# domino4_IPP.net
KiCad netlist of a schematic drawn in EAGLE
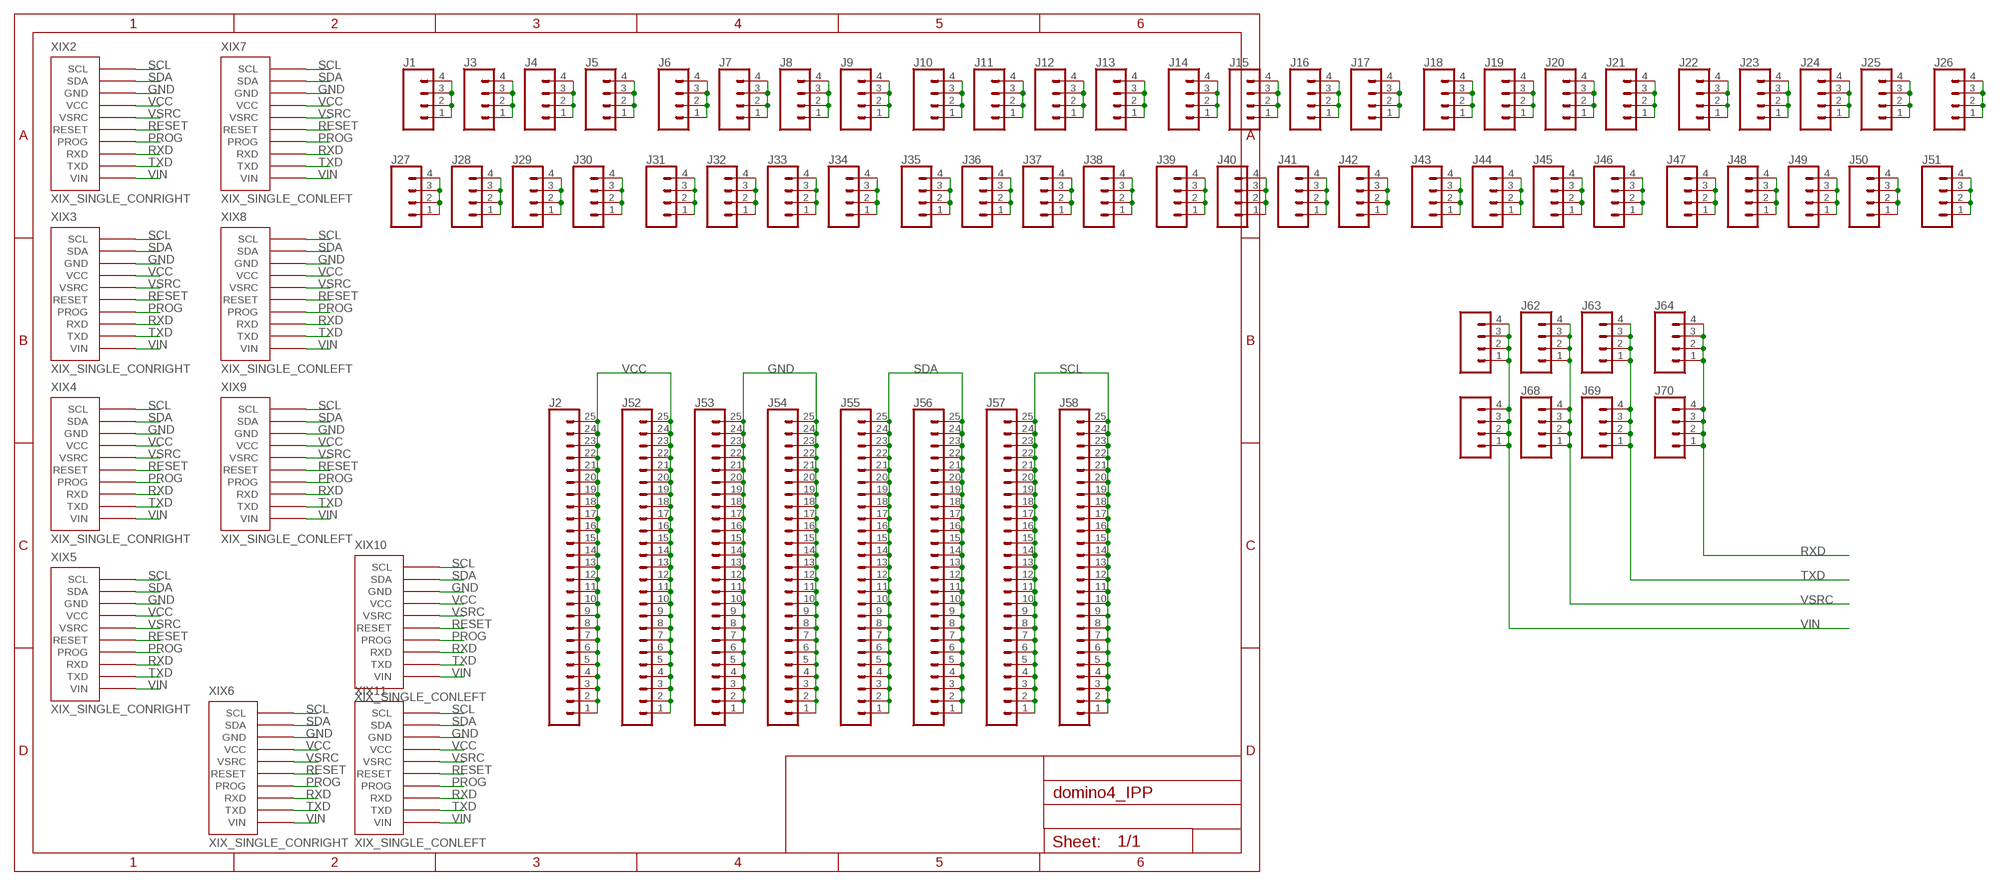
[diagram p0: schematic, sheet 1]

(export (version "E")
  (design (tool "Eeschema 10.0.6"))
  (components
    (comp (ref "J1")
      (value "CONN_04PTH")
      (footprint "eagle-import:1X04")
      (libsource (lib "eagle-import") (part "CONN_04PTH"))
    )
    (comp (ref "J2")
      (value "CONN_25")
      (footprint "eagle-import:1X25")
      (libsource (lib "eagle-import") (part "CONN_25"))
    )
    (comp (ref "J3")
      (value "CONN_04PTH")
      (footprint "eagle-import:1X04")
      (libsource (lib "eagle-import") (part "CONN_04PTH"))
    )
    (comp (ref "J4")
      (value "CONN_04PTH")
      (footprint "eagle-import:1X04")
      (libsource (lib "eagle-import") (part "CONN_04PTH"))
    )
    (comp (ref "J5")
      (value "CONN_04PTH")
      (footprint "eagle-import:1X04")
      (libsource (lib "eagle-import") (part "CONN_04PTH"))
    )
    (comp (ref "J6")
      (value "CONN_04PTH")
      (footprint "eagle-import:1X04")
      (libsource (lib "eagle-import") (part "CONN_04PTH"))
    )
    (comp (ref "J7")
      (value "CONN_04PTH")
      (footprint "eagle-import:1X04")
      (libsource (lib "eagle-import") (part "CONN_04PTH"))
    )
    (comp (ref "J8")
      (value "CONN_04PTH")
      (footprint "eagle-import:1X04")
      (libsource (lib "eagle-import") (part "CONN_04PTH"))
    )
    (comp (ref "J9")
      (value "CONN_04PTH")
      (footprint "eagle-import:1X04")
      (libsource (lib "eagle-import") (part "CONN_04PTH"))
    )
    (comp (ref "J10")
      (value "CONN_04PTH")
      (footprint "eagle-import:1X04")
      (libsource (lib "eagle-import") (part "CONN_04PTH"))
    )
    (comp (ref "J11")
      (value "CONN_04PTH")
      (footprint "eagle-import:1X04")
      (libsource (lib "eagle-import") (part "CONN_04PTH"))
    )
    (comp (ref "J12")
      (value "CONN_04PTH")
      (footprint "eagle-import:1X04")
      (libsource (lib "eagle-import") (part "CONN_04PTH"))
    )
    (comp (ref "J13")
      (value "CONN_04PTH")
      (footprint "eagle-import:1X04")
      (libsource (lib "eagle-import") (part "CONN_04PTH"))
    )
    (comp (ref "J14")
      (value "CONN_04PTH")
      (footprint "eagle-import:1X04")
      (libsource (lib "eagle-import") (part "CONN_04PTH"))
    )
    (comp (ref "J15")
      (value "CONN_04PTH")
      (footprint "eagle-import:1X04")
      (libsource (lib "eagle-import") (part "CONN_04PTH"))
    )
    (comp (ref "J16")
      (value "CONN_04PTH")
      (footprint "eagle-import:1X04")
      (libsource (lib "eagle-import") (part "CONN_04PTH"))
    )
    (comp (ref "J17")
      (value "CONN_04PTH")
      (footprint "eagle-import:1X04")
      (libsource (lib "eagle-import") (part "CONN_04PTH"))
    )
    (comp (ref "J18")
      (value "CONN_04PTH")
      (footprint "eagle-import:1X04")
      (libsource (lib "eagle-import") (part "CONN_04PTH"))
    )
    (comp (ref "J19")
      (value "CONN_04PTH")
      (footprint "eagle-import:1X04")
      (libsource (lib "eagle-import") (part "CONN_04PTH"))
    )
    (comp (ref "J20")
      (value "CONN_04PTH")
      (footprint "eagle-import:1X04")
      (libsource (lib "eagle-import") (part "CONN_04PTH"))
    )
    (comp (ref "J21")
      (value "CONN_04PTH")
      (footprint "eagle-import:1X04")
      (libsource (lib "eagle-import") (part "CONN_04PTH"))
    )
    (comp (ref "J22")
      (value "CONN_04PTH")
      (footprint "eagle-import:1X04")
      (libsource (lib "eagle-import") (part "CONN_04PTH"))
    )
    (comp (ref "J23")
      (value "CONN_04PTH")
      (footprint "eagle-import:1X04")
      (libsource (lib "eagle-import") (part "CONN_04PTH"))
    )
    (comp (ref "J24")
      (value "CONN_04PTH")
      (footprint "eagle-import:1X04")
      (libsource (lib "eagle-import") (part "CONN_04PTH"))
    )
    (comp (ref "J25")
      (value "CONN_04PTH")
      (footprint "eagle-import:1X04")
      (libsource (lib "eagle-import") (part "CONN_04PTH"))
    )
    (comp (ref "J26")
      (value "CONN_04PTH")
      (footprint "eagle-import:1X04")
      (libsource (lib "eagle-import") (part "CONN_04PTH"))
    )
    (comp (ref "J27")
      (value "CONN_04PTH")
      (footprint "eagle-import:1X04")
      (libsource (lib "eagle-import") (part "CONN_04PTH"))
    )
    (comp (ref "J28")
      (value "CONN_04PTH")
      (footprint "eagle-import:1X04")
      (libsource (lib "eagle-import") (part "CONN_04PTH"))
    )
    (comp (ref "J29")
      (value "CONN_04PTH")
      (footprint "eagle-import:1X04")
      (libsource (lib "eagle-import") (part "CONN_04PTH"))
    )
    (comp (ref "J30")
      (value "CONN_04PTH")
      (footprint "eagle-import:1X04")
      (libsource (lib "eagle-import") (part "CONN_04PTH"))
    )
    (comp (ref "J31")
      (value "CONN_04PTH")
      (footprint "eagle-import:1X04")
      (libsource (lib "eagle-import") (part "CONN_04PTH"))
    )
    (comp (ref "J32")
      (value "CONN_04PTH")
      (footprint "eagle-import:1X04")
      (libsource (lib "eagle-import") (part "CONN_04PTH"))
    )
    (comp (ref "J33")
      (value "CONN_04PTH")
      (footprint "eagle-import:1X04")
      (libsource (lib "eagle-import") (part "CONN_04PTH"))
    )
    (comp (ref "J34")
      (value "CONN_04PTH")
      (footprint "eagle-import:1X04")
      (libsource (lib "eagle-import") (part "CONN_04PTH"))
    )
    (comp (ref "J35")
      (value "CONN_04PTH")
      (footprint "eagle-import:1X04")
      (libsource (lib "eagle-import") (part "CONN_04PTH"))
    )
    (comp (ref "J36")
      (value "CONN_04PTH")
      (footprint "eagle-import:1X04")
      (libsource (lib "eagle-import") (part "CONN_04PTH"))
    )
    (comp (ref "J37")
      (value "CONN_04PTH")
      (footprint "eagle-import:1X04")
      (libsource (lib "eagle-import") (part "CONN_04PTH"))
    )
    (comp (ref "J38")
      (value "CONN_04PTH")
      (footprint "eagle-import:1X04")
      (libsource (lib "eagle-import") (part "CONN_04PTH"))
    )
    (comp (ref "J39")
      (value "CONN_04PTH")
      (footprint "eagle-import:1X04")
      (libsource (lib "eagle-import") (part "CONN_04PTH"))
    )
    (comp (ref "J40")
      (value "CONN_04PTH")
      (footprint "eagle-import:1X04")
      (libsource (lib "eagle-import") (part "CONN_04PTH"))
    )
    (comp (ref "J41")
      (value "CONN_04PTH")
      (footprint "eagle-import:1X04")
      (libsource (lib "eagle-import") (part "CONN_04PTH"))
    )
    (comp (ref "J42")
      (value "CONN_04PTH")
      (footprint "eagle-import:1X04")
      (libsource (lib "eagle-import") (part "CONN_04PTH"))
    )
    (comp (ref "J43")
      (value "CONN_04PTH")
      (footprint "eagle-import:1X04")
      (libsource (lib "eagle-import") (part "CONN_04PTH"))
    )
    (comp (ref "J44")
      (value "CONN_04PTH")
      (footprint "eagle-import:1X04")
      (libsource (lib "eagle-import") (part "CONN_04PTH"))
    )
    (comp (ref "J45")
      (value "CONN_04PTH")
      (footprint "eagle-import:1X04")
      (libsource (lib "eagle-import") (part "CONN_04PTH"))
    )
    (comp (ref "J46")
      (value "CONN_04PTH")
      (footprint "eagle-import:1X04")
      (libsource (lib "eagle-import") (part "CONN_04PTH"))
    )
    (comp (ref "J47")
      (value "CONN_04PTH")
      (footprint "eagle-import:1X04")
      (libsource (lib "eagle-import") (part "CONN_04PTH"))
    )
    (comp (ref "J48")
      (value "CONN_04PTH")
      (footprint "eagle-import:1X04")
      (libsource (lib "eagle-import") (part "CONN_04PTH"))
    )
    (comp (ref "J49")
      (value "CONN_04PTH")
      (footprint "eagle-import:1X04")
      (libsource (lib "eagle-import") (part "CONN_04PTH"))
    )
    (comp (ref "J50")
      (value "CONN_04PTH")
      (footprint "eagle-import:1X04")
      (libsource (lib "eagle-import") (part "CONN_04PTH"))
    )
    (comp (ref "J51")
      (value "CONN_04PTH")
      (footprint "eagle-import:1X04")
      (libsource (lib "eagle-import") (part "CONN_04PTH"))
    )
    (comp (ref "J52")
      (value "CONN_25")
      (footprint "eagle-import:1X25")
      (libsource (lib "eagle-import") (part "CONN_25"))
    )
    (comp (ref "J53")
      (value "CONN_25")
      (footprint "eagle-import:1X25")
      (libsource (lib "eagle-import") (part "CONN_25"))
    )
    (comp (ref "J54")
      (value "CONN_25")
      (footprint "eagle-import:1X25")
      (libsource (lib "eagle-import") (part "CONN_25"))
    )
    (comp (ref "J55")
      (value "CONN_25")
      (footprint "eagle-import:1X25")
      (libsource (lib "eagle-import") (part "CONN_25"))
    )
    (comp (ref "J56")
      (value "CONN_25")
      (footprint "eagle-import:1X25")
      (libsource (lib "eagle-import") (part "CONN_25"))
    )
    (comp (ref "J57")
      (value "CONN_25")
      (footprint "eagle-import:1X25")
      (libsource (lib "eagle-import") (part "CONN_25"))
    )
    (comp (ref "J58")
      (value "CONN_25")
      (footprint "eagle-import:1X25")
      (libsource (lib "eagle-import") (part "CONN_25"))
    )
    (comp (ref "J61")
      (value "CONN_04PTH")
      (footprint "eagle-import:1X04")
      (libsource (lib "eagle-import") (part "CONN_04PTH"))
    )
    (comp (ref "J62")
      (value "CONN_04PTH")
      (footprint "eagle-import:1X04")
      (libsource (lib "eagle-import") (part "CONN_04PTH"))
    )
    (comp (ref "J63")
      (value "CONN_04PTH")
      (footprint "eagle-import:1X04")
      (libsource (lib "eagle-import") (part "CONN_04PTH"))
    )
    (comp (ref "J64")
      (value "CONN_04PTH")
      (footprint "eagle-import:1X04")
      (libsource (lib "eagle-import") (part "CONN_04PTH"))
    )
    (comp (ref "J67")
      (value "CONN_04PTH")
      (footprint "eagle-import:1X04")
      (libsource (lib "eagle-import") (part "CONN_04PTH"))
    )
    (comp (ref "J68")
      (value "CONN_04PTH")
      (footprint "eagle-import:1X04")
      (libsource (lib "eagle-import") (part "CONN_04PTH"))
    )
    (comp (ref "J69")
      (value "CONN_04PTH")
      (footprint "eagle-import:1X04")
      (libsource (lib "eagle-import") (part "CONN_04PTH"))
    )
    (comp (ref "J70")
      (value "CONN_04PTH")
      (footprint "eagle-import:1X04")
      (libsource (lib "eagle-import") (part "CONN_04PTH"))
    )
    (comp (ref "XIX2")
      (value "XIX_SINGLE_CONRIGHT")
      (footprint "eagle-import:XIX_SINGLE_CON_RIGHT")
      (libsource (lib "eagle-import") (part "XIX_SINGLE_CONRIGHT"))
    )
    (comp (ref "XIX3")
      (value "XIX_SINGLE_CONRIGHT")
      (footprint "eagle-import:XIX_SINGLE_CON_RIGHT")
      (libsource (lib "eagle-import") (part "XIX_SINGLE_CONRIGHT"))
    )
    (comp (ref "XIX4")
      (value "XIX_SINGLE_CONRIGHT")
      (footprint "eagle-import:XIX_SINGLE_CON_RIGHT")
      (libsource (lib "eagle-import") (part "XIX_SINGLE_CONRIGHT"))
    )
    (comp (ref "XIX5")
      (value "XIX_SINGLE_CONRIGHT")
      (footprint "eagle-import:XIX_SINGLE_CON_RIGHT")
      (libsource (lib "eagle-import") (part "XIX_SINGLE_CONRIGHT"))
    )
    (comp (ref "XIX6")
      (value "XIX_SINGLE_CONRIGHT")
      (footprint "eagle-import:XIX_SINGLE_CON_RIGHT")
      (libsource (lib "eagle-import") (part "XIX_SINGLE_CONRIGHT"))
    )
    (comp (ref "XIX7")
      (value "XIX_SINGLE_CONLEFT")
      (footprint "eagle-import:XIX_SINGLE_CON_LEFT")
      (libsource (lib "eagle-import") (part "XIX_SINGLE_CONLEFT"))
    )
    (comp (ref "XIX8")
      (value "XIX_SINGLE_CONLEFT")
      (footprint "eagle-import:XIX_SINGLE_CON_LEFT")
      (libsource (lib "eagle-import") (part "XIX_SINGLE_CONLEFT"))
    )
    (comp (ref "XIX9")
      (value "XIX_SINGLE_CONLEFT")
      (footprint "eagle-import:XIX_SINGLE_CON_LEFT")
      (libsource (lib "eagle-import") (part "XIX_SINGLE_CONLEFT"))
    )
    (comp (ref "XIX10")
      (value "XIX_SINGLE_CONLEFT")
      (footprint "eagle-import:XIX_SINGLE_CON_LEFT")
      (libsource (lib "eagle-import") (part "XIX_SINGLE_CONLEFT"))
    )
    (comp (ref "XIX11")
      (value "XIX_SINGLE_CONLEFT")
      (footprint "eagle-import:XIX_SINGLE_CON_LEFT")
      (libsource (lib "eagle-import") (part "XIX_SINGLE_CONLEFT"))
    )
  )
  (nets
    (net (code "1") (name "/GND") (class "Default")
      (node (ref "J53") (pin "1") (pinfunction "1_1") (pintype "passive"))
      (node (ref "J53") (pin "10") (pinfunction "10_10") (pintype "passive"))
      (node (ref "J53") (pin "11") (pinfunction "11_11") (pintype "passive"))
      (node (ref "J53") (pin "12") (pinfunction "12_12") (pintype "passive"))
      (node (ref "J53") (pin "13") (pinfunction "13_13") (pintype "passive"))
      (node (ref "J53") (pin "14") (pinfunction "14_14") (pintype "passive"))
      (node (ref "J53") (pin "15") (pinfunction "15_15") (pintype "passive"))
      (node (ref "J53") (pin "16") (pinfunction "16_16") (pintype "passive"))
      (node (ref "J53") (pin "17") (pinfunction "17_17") (pintype "passive"))
      (node (ref "J53") (pin "18") (pinfunction "18_18") (pintype "passive"))
      (node (ref "J53") (pin "19") (pinfunction "19_19") (pintype "passive"))
      (node (ref "J53") (pin "2") (pinfunction "2_2") (pintype "passive"))
      (node (ref "J53") (pin "20") (pinfunction "20_20") (pintype "passive"))
      (node (ref "J53") (pin "21") (pinfunction "21_21") (pintype "passive"))
      (node (ref "J53") (pin "22") (pinfunction "22_22") (pintype "passive"))
      (node (ref "J53") (pin "23") (pinfunction "23_23") (pintype "passive"))
      (node (ref "J53") (pin "24") (pinfunction "24_24") (pintype "passive"))
      (node (ref "J53") (pin "25") (pinfunction "25_25") (pintype "passive"))
      (node (ref "J53") (pin "3") (pinfunction "3_3") (pintype "passive"))
      (node (ref "J53") (pin "4") (pinfunction "4_4") (pintype "passive"))
      (node (ref "J53") (pin "5") (pinfunction "5_5") (pintype "passive"))
      (node (ref "J53") (pin "6") (pinfunction "6_6") (pintype "passive"))
      (node (ref "J53") (pin "7") (pinfunction "7_7") (pintype "passive"))
      (node (ref "J53") (pin "8") (pinfunction "8_8") (pintype "passive"))
      (node (ref "J53") (pin "9") (pinfunction "9_9") (pintype "passive"))
      (node (ref "J54") (pin "1") (pinfunction "1_1") (pintype "passive"))
      (node (ref "J54") (pin "10") (pinfunction "10_10") (pintype "passive"))
      (node (ref "J54") (pin "11") (pinfunction "11_11") (pintype "passive"))
      (node (ref "J54") (pin "12") (pinfunction "12_12") (pintype "passive"))
      (node (ref "J54") (pin "13") (pinfunction "13_13") (pintype "passive"))
      (node (ref "J54") (pin "14") (pinfunction "14_14") (pintype "passive"))
      (node (ref "J54") (pin "15") (pinfunction "15_15") (pintype "passive"))
      (node (ref "J54") (pin "16") (pinfunction "16_16") (pintype "passive"))
      (node (ref "J54") (pin "17") (pinfunction "17_17") (pintype "passive"))
      (node (ref "J54") (pin "18") (pinfunction "18_18") (pintype "passive"))
      (node (ref "J54") (pin "19") (pinfunction "19_19") (pintype "passive"))
      (node (ref "J54") (pin "2") (pinfunction "2_2") (pintype "passive"))
      (node (ref "J54") (pin "20") (pinfunction "20_20") (pintype "passive"))
      (node (ref "J54") (pin "21") (pinfunction "21_21") (pintype "passive"))
      (node (ref "J54") (pin "22") (pinfunction "22_22") (pintype "passive"))
      (node (ref "J54") (pin "23") (pinfunction "23_23") (pintype "passive"))
      (node (ref "J54") (pin "24") (pinfunction "24_24") (pintype "passive"))
      (node (ref "J54") (pin "25") (pinfunction "25_25") (pintype "passive"))
      (node (ref "J54") (pin "3") (pinfunction "3_3") (pintype "passive"))
      (node (ref "J54") (pin "4") (pinfunction "4_4") (pintype "passive"))
      (node (ref "J54") (pin "5") (pinfunction "5_5") (pintype "passive"))
      (node (ref "J54") (pin "6") (pinfunction "6_6") (pintype "passive"))
      (node (ref "J54") (pin "7") (pinfunction "7_7") (pintype "passive"))
      (node (ref "J54") (pin "8") (pinfunction "8_8") (pintype "passive"))
      (node (ref "J54") (pin "9") (pinfunction "9_9") (pintype "passive"))
      (node (ref "XIX10") (pin "GND@1") (pinfunction "GND_GND@1") (pintype "power_in"))
      (node (ref "XIX11") (pin "GND@1") (pinfunction "GND_GND@1") (pintype "power_in"))
      (node (ref "XIX2") (pin "GND@4") (pinfunction "GND_GND@4") (pintype "power_in"))
      (node (ref "XIX3") (pin "GND@4") (pinfunction "GND_GND@4") (pintype "power_in"))
      (node (ref "XIX4") (pin "GND@4") (pinfunction "GND_GND@4") (pintype "power_in"))
      (node (ref "XIX5") (pin "GND@4") (pinfunction "GND_GND@4") (pintype "power_in"))
      (node (ref "XIX6") (pin "GND@4") (pinfunction "GND_GND@4") (pintype "power_in"))
      (node (ref "XIX7") (pin "GND@1") (pinfunction "GND_GND@1") (pintype "power_in"))
      (node (ref "XIX8") (pin "GND@1") (pinfunction "GND_GND@1") (pintype "power_in"))
      (node (ref "XIX9") (pin "GND@1") (pinfunction "GND_GND@1") (pintype "power_in"))
    )
    (net (code "2") (name "/PROG") (class "Default")
      (node (ref "XIX10") (pin "PROG@2") (pinfunction "PROG_PROG@2") (pintype "bidirectional"))
      (node (ref "XIX11") (pin "PROG@2") (pinfunction "PROG_PROG@2") (pintype "bidirectional"))
      (node (ref "XIX2") (pin "PROG@8") (pinfunction "PROG_PROG@8") (pintype "bidirectional"))
      (node (ref "XIX3") (pin "PROG@8") (pinfunction "PROG_PROG@8") (pintype "bidirectional"))
      (node (ref "XIX4") (pin "PROG@8") (pinfunction "PROG_PROG@8") (pintype "bidirectional"))
      (node (ref "XIX5") (pin "PROG@8") (pinfunction "PROG_PROG@8") (pintype "bidirectional"))
      (node (ref "XIX6") (pin "PROG@8") (pinfunction "PROG_PROG@8") (pintype "bidirectional"))
      (node (ref "XIX7") (pin "PROG@2") (pinfunction "PROG_PROG@2") (pintype "bidirectional"))
      (node (ref "XIX8") (pin "PROG@2") (pinfunction "PROG_PROG@2") (pintype "bidirectional"))
      (node (ref "XIX9") (pin "PROG@2") (pinfunction "PROG_PROG@2") (pintype "bidirectional"))
    )
    (net (code "3") (name "/RESET") (class "Default")
      (node (ref "XIX10") (pin "RESET@2") (pinfunction "RESET_RESET@2") (pintype "bidirectional"))
      (node (ref "XIX11") (pin "RESET@2") (pinfunction "RESET_RESET@2") (pintype "bidirectional"))
      (node (ref "XIX2") (pin "RESET@8") (pinfunction "RESET_RESET@8") (pintype "bidirectional"))
      (node (ref "XIX3") (pin "RESET@8") (pinfunction "RESET_RESET@8") (pintype "bidirectional"))
      (node (ref "XIX4") (pin "RESET@8") (pinfunction "RESET_RESET@8") (pintype "bidirectional"))
      (node (ref "XIX5") (pin "RESET@8") (pinfunction "RESET_RESET@8") (pintype "bidirectional"))
      (node (ref "XIX6") (pin "RESET@8") (pinfunction "RESET_RESET@8") (pintype "bidirectional"))
      (node (ref "XIX7") (pin "RESET@2") (pinfunction "RESET_RESET@2") (pintype "bidirectional"))
      (node (ref "XIX8") (pin "RESET@2") (pinfunction "RESET_RESET@2") (pintype "bidirectional"))
      (node (ref "XIX9") (pin "RESET@2") (pinfunction "RESET_RESET@2") (pintype "bidirectional"))
    )
    (net (code "4") (name "/RXD") (class "Default")
      (node (ref "J64") (pin "1") (pinfunction "1_1") (pintype "passive"))
      (node (ref "J64") (pin "2") (pinfunction "2_2") (pintype "passive"))
      (node (ref "J64") (pin "3") (pinfunction "3_3") (pintype "passive"))
      (node (ref "J64") (pin "4") (pinfunction "4_4") (pintype "passive"))
      (node (ref "J70") (pin "1") (pinfunction "1_1") (pintype "passive"))
      (node (ref "J70") (pin "2") (pinfunction "2_2") (pintype "passive"))
      (node (ref "J70") (pin "3") (pinfunction "3_3") (pintype "passive"))
      (node (ref "J70") (pin "4") (pinfunction "4_4") (pintype "passive"))
      (node (ref "XIX10") (pin "RXD@2") (pinfunction "RXD_RXD@2") (pintype "bidirectional"))
      (node (ref "XIX11") (pin "RXD@2") (pinfunction "RXD_RXD@2") (pintype "bidirectional"))
      (node (ref "XIX2") (pin "RXD@8") (pinfunction "RXD_RXD@8") (pintype "bidirectional"))
      (node (ref "XIX3") (pin "RXD@8") (pinfunction "RXD_RXD@8") (pintype "bidirectional"))
      (node (ref "XIX4") (pin "RXD@8") (pinfunction "RXD_RXD@8") (pintype "bidirectional"))
      (node (ref "XIX5") (pin "RXD@8") (pinfunction "RXD_RXD@8") (pintype "bidirectional"))
      (node (ref "XIX6") (pin "RXD@8") (pinfunction "RXD_RXD@8") (pintype "bidirectional"))
      (node (ref "XIX7") (pin "RXD@2") (pinfunction "RXD_RXD@2") (pintype "bidirectional"))
      (node (ref "XIX8") (pin "RXD@2") (pinfunction "RXD_RXD@2") (pintype "bidirectional"))
      (node (ref "XIX9") (pin "RXD@2") (pinfunction "RXD_RXD@2") (pintype "bidirectional"))
    )
    (net (code "5") (name "/SCL") (class "Default")
      (node (ref "J57") (pin "1") (pinfunction "1_1") (pintype "passive"))
      (node (ref "J57") (pin "10") (pinfunction "10_10") (pintype "passive"))
      (node (ref "J57") (pin "11") (pinfunction "11_11") (pintype "passive"))
      (node (ref "J57") (pin "12") (pinfunction "12_12") (pintype "passive"))
      (node (ref "J57") (pin "13") (pinfunction "13_13") (pintype "passive"))
      (node (ref "J57") (pin "14") (pinfunction "14_14") (pintype "passive"))
      (node (ref "J57") (pin "15") (pinfunction "15_15") (pintype "passive"))
      (node (ref "J57") (pin "16") (pinfunction "16_16") (pintype "passive"))
      (node (ref "J57") (pin "17") (pinfunction "17_17") (pintype "passive"))
      (node (ref "J57") (pin "18") (pinfunction "18_18") (pintype "passive"))
      (node (ref "J57") (pin "19") (pinfunction "19_19") (pintype "passive"))
      (node (ref "J57") (pin "2") (pinfunction "2_2") (pintype "passive"))
      (node (ref "J57") (pin "20") (pinfunction "20_20") (pintype "passive"))
      (node (ref "J57") (pin "21") (pinfunction "21_21") (pintype "passive"))
      (node (ref "J57") (pin "22") (pinfunction "22_22") (pintype "passive"))
      (node (ref "J57") (pin "23") (pinfunction "23_23") (pintype "passive"))
      (node (ref "J57") (pin "24") (pinfunction "24_24") (pintype "passive"))
      (node (ref "J57") (pin "25") (pinfunction "25_25") (pintype "passive"))
      (node (ref "J57") (pin "3") (pinfunction "3_3") (pintype "passive"))
      (node (ref "J57") (pin "4") (pinfunction "4_4") (pintype "passive"))
      (node (ref "J57") (pin "5") (pinfunction "5_5") (pintype "passive"))
      (node (ref "J57") (pin "6") (pinfunction "6_6") (pintype "passive"))
      (node (ref "J57") (pin "7") (pinfunction "7_7") (pintype "passive"))
      (node (ref "J57") (pin "8") (pinfunction "8_8") (pintype "passive"))
      (node (ref "J57") (pin "9") (pinfunction "9_9") (pintype "passive"))
      (node (ref "J58") (pin "1") (pinfunction "1_1") (pintype "passive"))
      (node (ref "J58") (pin "10") (pinfunction "10_10") (pintype "passive"))
      (node (ref "J58") (pin "11") (pinfunction "11_11") (pintype "passive"))
      (node (ref "J58") (pin "12") (pinfunction "12_12") (pintype "passive"))
      (node (ref "J58") (pin "13") (pinfunction "13_13") (pintype "passive"))
      (node (ref "J58") (pin "14") (pinfunction "14_14") (pintype "passive"))
      (node (ref "J58") (pin "15") (pinfunction "15_15") (pintype "passive"))
      (node (ref "J58") (pin "16") (pinfunction "16_16") (pintype "passive"))
      (node (ref "J58") (pin "17") (pinfunction "17_17") (pintype "passive"))
      (node (ref "J58") (pin "18") (pinfunction "18_18") (pintype "passive"))
      (node (ref "J58") (pin "19") (pinfunction "19_19") (pintype "passive"))
      (node (ref "J58") (pin "2") (pinfunction "2_2") (pintype "passive"))
      (node (ref "J58") (pin "20") (pinfunction "20_20") (pintype "passive"))
      (node (ref "J58") (pin "21") (pinfunction "21_21") (pintype "passive"))
      (node (ref "J58") (pin "22") (pinfunction "22_22") (pintype "passive"))
      (node (ref "J58") (pin "23") (pinfunction "23_23") (pintype "passive"))
      (node (ref "J58") (pin "24") (pinfunction "24_24") (pintype "passive"))
      (node (ref "J58") (pin "25") (pinfunction "25_25") (pintype "passive"))
      (node (ref "J58") (pin "3") (pinfunction "3_3") (pintype "passive"))
      (node (ref "J58") (pin "4") (pinfunction "4_4") (pintype "passive"))
      (node (ref "J58") (pin "5") (pinfunction "5_5") (pintype "passive"))
      (node (ref "J58") (pin "6") (pinfunction "6_6") (pintype "passive"))
      (node (ref "J58") (pin "7") (pinfunction "7_7") (pintype "passive"))
      (node (ref "J58") (pin "8") (pinfunction "8_8") (pintype "passive"))
      (node (ref "J58") (pin "9") (pinfunction "9_9") (pintype "passive"))
      (node (ref "XIX10") (pin "SCL@1") (pinfunction "SCL_SCL@1") (pintype "bidirectional"))
      (node (ref "XIX11") (pin "SCL@1") (pinfunction "SCL_SCL@1") (pintype "bidirectional"))
      (node (ref "XIX2") (pin "SCL@4") (pinfunction "SCL_SCL@4") (pintype "bidirectional"))
      (node (ref "XIX3") (pin "SCL@4") (pinfunction "SCL_SCL@4") (pintype "bidirectional"))
      (node (ref "XIX4") (pin "SCL@4") (pinfunction "SCL_SCL@4") (pintype "bidirectional"))
      (node (ref "XIX5") (pin "SCL@4") (pinfunction "SCL_SCL@4") (pintype "bidirectional"))
      (node (ref "XIX6") (pin "SCL@4") (pinfunction "SCL_SCL@4") (pintype "bidirectional"))
      (node (ref "XIX7") (pin "SCL@1") (pinfunction "SCL_SCL@1") (pintype "bidirectional"))
      (node (ref "XIX8") (pin "SCL@1") (pinfunction "SCL_SCL@1") (pintype "bidirectional"))
      (node (ref "XIX9") (pin "SCL@1") (pinfunction "SCL_SCL@1") (pintype "bidirectional"))
    )
    (net (code "6") (name "/SDA") (class "Default")
      (node (ref "J55") (pin "1") (pinfunction "1_1") (pintype "passive"))
      (node (ref "J55") (pin "10") (pinfunction "10_10") (pintype "passive"))
      (node (ref "J55") (pin "11") (pinfunction "11_11") (pintype "passive"))
      (node (ref "J55") (pin "12") (pinfunction "12_12") (pintype "passive"))
      (node (ref "J55") (pin "13") (pinfunction "13_13") (pintype "passive"))
      (node (ref "J55") (pin "14") (pinfunction "14_14") (pintype "passive"))
      (node (ref "J55") (pin "15") (pinfunction "15_15") (pintype "passive"))
      (node (ref "J55") (pin "16") (pinfunction "16_16") (pintype "passive"))
      (node (ref "J55") (pin "17") (pinfunction "17_17") (pintype "passive"))
      (node (ref "J55") (pin "18") (pinfunction "18_18") (pintype "passive"))
      (node (ref "J55") (pin "19") (pinfunction "19_19") (pintype "passive"))
      (node (ref "J55") (pin "2") (pinfunction "2_2") (pintype "passive"))
      (node (ref "J55") (pin "20") (pinfunction "20_20") (pintype "passive"))
      (node (ref "J55") (pin "21") (pinfunction "21_21") (pintype "passive"))
      (node (ref "J55") (pin "22") (pinfunction "22_22") (pintype "passive"))
      (node (ref "J55") (pin "23") (pinfunction "23_23") (pintype "passive"))
      (node (ref "J55") (pin "24") (pinfunction "24_24") (pintype "passive"))
      (node (ref "J55") (pin "25") (pinfunction "25_25") (pintype "passive"))
      (node (ref "J55") (pin "3") (pinfunction "3_3") (pintype "passive"))
      (node (ref "J55") (pin "4") (pinfunction "4_4") (pintype "passive"))
      (node (ref "J55") (pin "5") (pinfunction "5_5") (pintype "passive"))
      (node (ref "J55") (pin "6") (pinfunction "6_6") (pintype "passive"))
      (node (ref "J55") (pin "7") (pinfunction "7_7") (pintype "passive"))
      (node (ref "J55") (pin "8") (pinfunction "8_8") (pintype "passive"))
      (node (ref "J55") (pin "9") (pinfunction "9_9") (pintype "passive"))
      (node (ref "J56") (pin "1") (pinfunction "1_1") (pintype "passive"))
      (node (ref "J56") (pin "10") (pinfunction "10_10") (pintype "passive"))
      (node (ref "J56") (pin "11") (pinfunction "11_11") (pintype "passive"))
      (node (ref "J56") (pin "12") (pinfunction "12_12") (pintype "passive"))
      (node (ref "J56") (pin "13") (pinfunction "13_13") (pintype "passive"))
      (node (ref "J56") (pin "14") (pinfunction "14_14") (pintype "passive"))
      (node (ref "J56") (pin "15") (pinfunction "15_15") (pintype "passive"))
      (node (ref "J56") (pin "16") (pinfunction "16_16") (pintype "passive"))
      (node (ref "J56") (pin "17") (pinfunction "17_17") (pintype "passive"))
      (node (ref "J56") (pin "18") (pinfunction "18_18") (pintype "passive"))
      (node (ref "J56") (pin "19") (pinfunction "19_19") (pintype "passive"))
      (node (ref "J56") (pin "2") (pinfunction "2_2") (pintype "passive"))
      (node (ref "J56") (pin "20") (pinfunction "20_20") (pintype "passive"))
      (node (ref "J56") (pin "21") (pinfunction "21_21") (pintype "passive"))
      (node (ref "J56") (pin "22") (pinfunction "22_22") (pintype "passive"))
      (node (ref "J56") (pin "23") (pinfunction "23_23") (pintype "passive"))
      (node (ref "J56") (pin "24") (pinfunction "24_24") (pintype "passive"))
      (node (ref "J56") (pin "25") (pinfunction "25_25") (pintype "passive"))
      (node (ref "J56") (pin "3") (pinfunction "3_3") (pintype "passive"))
      (node (ref "J56") (pin "4") (pinfunction "4_4") (pintype "passive"))
      (node (ref "J56") (pin "5") (pinfunction "5_5") (pintype "passive"))
      (node (ref "J56") (pin "6") (pinfunction "6_6") (pintype "passive"))
      (node (ref "J56") (pin "7") (pinfunction "7_7") (pintype "passive"))
      (node (ref "J56") (pin "8") (pinfunction "8_8") (pintype "passive"))
      (node (ref "J56") (pin "9") (pinfunction "9_9") (pintype "passive"))
      (node (ref "XIX10") (pin "SDA@1") (pinfunction "SDA_SDA@1") (pintype "bidirectional"))
      (node (ref "XIX11") (pin "SDA@1") (pinfunction "SDA_SDA@1") (pintype "bidirectional"))
      (node (ref "XIX2") (pin "SDA@4") (pinfunction "SDA_SDA@4") (pintype "bidirectional"))
      (node (ref "XIX3") (pin "SDA@4") (pinfunction "SDA_SDA@4") (pintype "bidirectional"))
      (node (ref "XIX4") (pin "SDA@4") (pinfunction "SDA_SDA@4") (pintype "bidirectional"))
      (node (ref "XIX5") (pin "SDA@4") (pinfunction "SDA_SDA@4") (pintype "bidirectional"))
      (node (ref "XIX6") (pin "SDA@4") (pinfunction "SDA_SDA@4") (pintype "bidirectional"))
      (node (ref "XIX7") (pin "SDA@1") (pinfunction "SDA_SDA@1") (pintype "bidirectional"))
      (node (ref "XIX8") (pin "SDA@1") (pinfunction "SDA_SDA@1") (pintype "bidirectional"))
      (node (ref "XIX9") (pin "SDA@1") (pinfunction "SDA_SDA@1") (pintype "bidirectional"))
    )
    (net (code "7") (name "/TXD") (class "Default")
      (node (ref "J63") (pin "1") (pinfunction "1_1") (pintype "passive"))
      (node (ref "J63") (pin "2") (pinfunction "2_2") (pintype "passive"))
      (node (ref "J63") (pin "3") (pinfunction "3_3") (pintype "passive"))
      (node (ref "J63") (pin "4") (pinfunction "4_4") (pintype "passive"))
      (node (ref "J69") (pin "1") (pinfunction "1_1") (pintype "passive"))
      (node (ref "J69") (pin "2") (pinfunction "2_2") (pintype "passive"))
      (node (ref "J69") (pin "3") (pinfunction "3_3") (pintype "passive"))
      (node (ref "J69") (pin "4") (pinfunction "4_4") (pintype "passive"))
      (node (ref "XIX10") (pin "TXD@2") (pinfunction "TXD_TXD@2") (pintype "bidirectional"))
      (node (ref "XIX11") (pin "TXD@2") (pinfunction "TXD_TXD@2") (pintype "bidirectional"))
      (node (ref "XIX2") (pin "TXD@8") (pinfunction "TXD_TXD@8") (pintype "bidirectional"))
      (node (ref "XIX3") (pin "TXD@8") (pinfunction "TXD_TXD@8") (pintype "bidirectional"))
      (node (ref "XIX4") (pin "TXD@8") (pinfunction "TXD_TXD@8") (pintype "bidirectional"))
      (node (ref "XIX5") (pin "TXD@8") (pinfunction "TXD_TXD@8") (pintype "bidirectional"))
      (node (ref "XIX6") (pin "TXD@8") (pinfunction "TXD_TXD@8") (pintype "bidirectional"))
      (node (ref "XIX7") (pin "TXD@2") (pinfunction "TXD_TXD@2") (pintype "bidirectional"))
      (node (ref "XIX8") (pin "TXD@2") (pinfunction "TXD_TXD@2") (pintype "bidirectional"))
      (node (ref "XIX9") (pin "TXD@2") (pinfunction "TXD_TXD@2") (pintype "bidirectional"))
    )
    (net (code "8") (name "/VCC") (class "Default")
      (node (ref "J2") (pin "1") (pinfunction "1_1") (pintype "passive"))
      (node (ref "J2") (pin "10") (pinfunction "10_10") (pintype "passive"))
      (node (ref "J2") (pin "11") (pinfunction "11_11") (pintype "passive"))
      (node (ref "J2") (pin "12") (pinfunction "12_12") (pintype "passive"))
      (node (ref "J2") (pin "13") (pinfunction "13_13") (pintype "passive"))
      (node (ref "J2") (pin "14") (pinfunction "14_14") (pintype "passive"))
      (node (ref "J2") (pin "15") (pinfunction "15_15") (pintype "passive"))
      (node (ref "J2") (pin "16") (pinfunction "16_16") (pintype "passive"))
      (node (ref "J2") (pin "17") (pinfunction "17_17") (pintype "passive"))
      (node (ref "J2") (pin "18") (pinfunction "18_18") (pintype "passive"))
      (node (ref "J2") (pin "19") (pinfunction "19_19") (pintype "passive"))
      (node (ref "J2") (pin "2") (pinfunction "2_2") (pintype "passive"))
      (node (ref "J2") (pin "20") (pinfunction "20_20") (pintype "passive"))
      (node (ref "J2") (pin "21") (pinfunction "21_21") (pintype "passive"))
      (node (ref "J2") (pin "22") (pinfunction "22_22") (pintype "passive"))
      (node (ref "J2") (pin "23") (pinfunction "23_23") (pintype "passive"))
      (node (ref "J2") (pin "24") (pinfunction "24_24") (pintype "passive"))
      (node (ref "J2") (pin "25") (pinfunction "25_25") (pintype "passive"))
      (node (ref "J2") (pin "3") (pinfunction "3_3") (pintype "passive"))
      (node (ref "J2") (pin "4") (pinfunction "4_4") (pintype "passive"))
      (node (ref "J2") (pin "5") (pinfunction "5_5") (pintype "passive"))
      (node (ref "J2") (pin "6") (pinfunction "6_6") (pintype "passive"))
      (node (ref "J2") (pin "7") (pinfunction "7_7") (pintype "passive"))
      (node (ref "J2") (pin "8") (pinfunction "8_8") (pintype "passive"))
      (node (ref "J2") (pin "9") (pinfunction "9_9") (pintype "passive"))
      (node (ref "J52") (pin "1") (pinfunction "1_1") (pintype "passive"))
      (node (ref "J52") (pin "10") (pinfunction "10_10") (pintype "passive"))
      (node (ref "J52") (pin "11") (pinfunction "11_11") (pintype "passive"))
      (node (ref "J52") (pin "12") (pinfunction "12_12") (pintype "passive"))
      (node (ref "J52") (pin "13") (pinfunction "13_13") (pintype "passive"))
      (node (ref "J52") (pin "14") (pinfunction "14_14") (pintype "passive"))
      (node (ref "J52") (pin "15") (pinfunction "15_15") (pintype "passive"))
      (node (ref "J52") (pin "16") (pinfunction "16_16") (pintype "passive"))
      (node (ref "J52") (pin "17") (pinfunction "17_17") (pintype "passive"))
      (node (ref "J52") (pin "18") (pinfunction "18_18") (pintype "passive"))
      (node (ref "J52") (pin "19") (pinfunction "19_19") (pintype "passive"))
      (node (ref "J52") (pin "2") (pinfunction "2_2") (pintype "passive"))
      (node (ref "J52") (pin "20") (pinfunction "20_20") (pintype "passive"))
      (node (ref "J52") (pin "21") (pinfunction "21_21") (pintype "passive"))
      (node (ref "J52") (pin "22") (pinfunction "22_22") (pintype "passive"))
      (node (ref "J52") (pin "23") (pinfunction "23_23") (pintype "passive"))
      (node (ref "J52") (pin "24") (pinfunction "24_24") (pintype "passive"))
      (node (ref "J52") (pin "25") (pinfunction "25_25") (pintype "passive"))
      (node (ref "J52") (pin "3") (pinfunction "3_3") (pintype "passive"))
      (node (ref "J52") (pin "4") (pinfunction "4_4") (pintype "passive"))
      (node (ref "J52") (pin "5") (pinfunction "5_5") (pintype "passive"))
      (node (ref "J52") (pin "6") (pinfunction "6_6") (pintype "passive"))
      (node (ref "J52") (pin "7") (pinfunction "7_7") (pintype "passive"))
      (node (ref "J52") (pin "8") (pinfunction "8_8") (pintype "passive"))
      (node (ref "J52") (pin "9") (pinfunction "9_9") (pintype "passive"))
      (node (ref "XIX10") (pin "VCC@1") (pinfunction "VCC_VCC@1") (pintype "power_in"))
      (node (ref "XIX11") (pin "VCC@1") (pinfunction "VCC_VCC@1") (pintype "power_in"))
      (node (ref "XIX2") (pin "VCC@4") (pinfunction "VCC_VCC@4") (pintype "power_in"))
      (node (ref "XIX3") (pin "VCC@4") (pinfunction "VCC_VCC@4") (pintype "power_in"))
      (node (ref "XIX4") (pin "VCC@4") (pinfunction "VCC_VCC@4") (pintype "power_in"))
      (node (ref "XIX5") (pin "VCC@4") (pinfunction "VCC_VCC@4") (pintype "power_in"))
      (node (ref "XIX6") (pin "VCC@4") (pinfunction "VCC_VCC@4") (pintype "power_in"))
      (node (ref "XIX7") (pin "VCC@1") (pinfunction "VCC_VCC@1") (pintype "power_in"))
      (node (ref "XIX8") (pin "VCC@1") (pinfunction "VCC_VCC@1") (pintype "power_in"))
      (node (ref "XIX9") (pin "VCC@1") (pinfunction "VCC_VCC@1") (pintype "power_in"))
    )
    (net (code "9") (name "/VIN") (class "Default")
      (node (ref "J61") (pin "1") (pinfunction "1_1") (pintype "passive"))
      (node (ref "J61") (pin "2") (pinfunction "2_2") (pintype "passive"))
      (node (ref "J61") (pin "3") (pinfunction "3_3") (pintype "passive"))
      (node (ref "J61") (pin "4") (pinfunction "4_4") (pintype "passive"))
      (node (ref "J67") (pin "1") (pinfunction "1_1") (pintype "passive"))
      (node (ref "J67") (pin "2") (pinfunction "2_2") (pintype "passive"))
      (node (ref "J67") (pin "3") (pinfunction "3_3") (pintype "passive"))
      (node (ref "J67") (pin "4") (pinfunction "4_4") (pintype "passive"))
      (node (ref "XIX10") (pin "VRAW@2") (pinfunction "VIN_VRAW@2") (pintype "power_in"))
      (node (ref "XIX11") (pin "VRAW@2") (pinfunction "VIN_VRAW@2") (pintype "power_in"))
      (node (ref "XIX2") (pin "VRAW@8") (pinfunction "VIN_VRAW@8") (pintype "power_in"))
      (node (ref "XIX3") (pin "VRAW@8") (pinfunction "VIN_VRAW@8") (pintype "power_in"))
      (node (ref "XIX4") (pin "VRAW@8") (pinfunction "VIN_VRAW@8") (pintype "power_in"))
      (node (ref "XIX5") (pin "VRAW@8") (pinfunction "VIN_VRAW@8") (pintype "power_in"))
      (node (ref "XIX6") (pin "VRAW@8") (pinfunction "VIN_VRAW@8") (pintype "power_in"))
      (node (ref "XIX7") (pin "VRAW@2") (pinfunction "VIN_VRAW@2") (pintype "power_in"))
      (node (ref "XIX8") (pin "VRAW@2") (pinfunction "VIN_VRAW@2") (pintype "power_in"))
      (node (ref "XIX9") (pin "VRAW@2") (pinfunction "VIN_VRAW@2") (pintype "power_in"))
    )
    (net (code "10") (name "/VSRC") (class "Default")
      (node (ref "J62") (pin "1") (pinfunction "1_1") (pintype "passive"))
      (node (ref "J62") (pin "2") (pinfunction "2_2") (pintype "passive"))
      (node (ref "J62") (pin "3") (pinfunction "3_3") (pintype "passive"))
      (node (ref "J62") (pin "4") (pinfunction "4_4") (pintype "passive"))
      (node (ref "J68") (pin "1") (pinfunction "1_1") (pintype "passive"))
      (node (ref "J68") (pin "2") (pinfunction "2_2") (pintype "passive"))
      (node (ref "J68") (pin "3") (pinfunction "3_3") (pintype "passive"))
      (node (ref "J68") (pin "4") (pinfunction "4_4") (pintype "passive"))
      (node (ref "XIX10") (pin "VBAT@1") (pinfunction "VSRC_VBAT@1") (pintype "power_in"))
      (node (ref "XIX11") (pin "VBAT@1") (pinfunction "VSRC_VBAT@1") (pintype "power_in"))
      (node (ref "XIX2") (pin "VBAT@4") (pinfunction "VSRC_VBAT@4") (pintype "power_in"))
      (node (ref "XIX3") (pin "VBAT@4") (pinfunction "VSRC_VBAT@4") (pintype "power_in"))
      (node (ref "XIX4") (pin "VBAT@4") (pinfunction "VSRC_VBAT@4") (pintype "power_in"))
      (node (ref "XIX5") (pin "VBAT@4") (pinfunction "VSRC_VBAT@4") (pintype "power_in"))
      (node (ref "XIX6") (pin "VBAT@4") (pinfunction "VSRC_VBAT@4") (pintype "power_in"))
      (node (ref "XIX7") (pin "VBAT@1") (pinfunction "VSRC_VBAT@1") (pintype "power_in"))
      (node (ref "XIX8") (pin "VBAT@1") (pinfunction "VSRC_VBAT@1") (pintype "power_in"))
      (node (ref "XIX9") (pin "VBAT@1") (pinfunction "VSRC_VBAT@1") (pintype "power_in"))
    )
    (net (code "11") (name "Net-(J1-Pad1)") (class "Default")
      (node (ref "J1") (pin "1") (pinfunction "1_1") (pintype "passive"))
      (node (ref "J1") (pin "2") (pinfunction "2_2") (pintype "passive"))
      (node (ref "J1") (pin "3") (pinfunction "3_3") (pintype "passive"))
      (node (ref "J1") (pin "4") (pinfunction "4_4") (pintype "passive"))
    )
    (net (code "12") (name "Net-(J3-Pad1)") (class "Default")
      (node (ref "J3") (pin "1") (pinfunction "1_1") (pintype "passive"))
      (node (ref "J3") (pin "2") (pinfunction "2_2") (pintype "passive"))
      (node (ref "J3") (pin "3") (pinfunction "3_3") (pintype "passive"))
      (node (ref "J3") (pin "4") (pinfunction "4_4") (pintype "passive"))
    )
    (net (code "13") (name "Net-(J4-Pad1)") (class "Default")
      (node (ref "J4") (pin "1") (pinfunction "1_1") (pintype "passive"))
      (node (ref "J4") (pin "2") (pinfunction "2_2") (pintype "passive"))
      (node (ref "J4") (pin "3") (pinfunction "3_3") (pintype "passive"))
      (node (ref "J4") (pin "4") (pinfunction "4_4") (pintype "passive"))
    )
    (net (code "14") (name "Net-(J5-Pad1)") (class "Default")
      (node (ref "J5") (pin "1") (pinfunction "1_1") (pintype "passive"))
      (node (ref "J5") (pin "2") (pinfunction "2_2") (pintype "passive"))
      (node (ref "J5") (pin "3") (pinfunction "3_3") (pintype "passive"))
      (node (ref "J5") (pin "4") (pinfunction "4_4") (pintype "passive"))
    )
    (net (code "15") (name "Net-(J6-Pad1)") (class "Default")
      (node (ref "J6") (pin "1") (pinfunction "1_1") (pintype "passive"))
      (node (ref "J6") (pin "2") (pinfunction "2_2") (pintype "passive"))
      (node (ref "J6") (pin "3") (pinfunction "3_3") (pintype "passive"))
      (node (ref "J6") (pin "4") (pinfunction "4_4") (pintype "passive"))
    )
    (net (code "16") (name "Net-(J7-Pad1)") (class "Default")
      (node (ref "J7") (pin "1") (pinfunction "1_1") (pintype "passive"))
      (node (ref "J7") (pin "2") (pinfunction "2_2") (pintype "passive"))
      (node (ref "J7") (pin "3") (pinfunction "3_3") (pintype "passive"))
      (node (ref "J7") (pin "4") (pinfunction "4_4") (pintype "passive"))
    )
    (net (code "17") (name "Net-(J8-Pad1)") (class "Default")
      (node (ref "J8") (pin "1") (pinfunction "1_1") (pintype "passive"))
      (node (ref "J8") (pin "2") (pinfunction "2_2") (pintype "passive"))
      (node (ref "J8") (pin "3") (pinfunction "3_3") (pintype "passive"))
      (node (ref "J8") (pin "4") (pinfunction "4_4") (pintype "passive"))
    )
    (net (code "18") (name "Net-(J9-Pad1)") (class "Default")
      (node (ref "J9") (pin "1") (pinfunction "1_1") (pintype "passive"))
      (node (ref "J9") (pin "2") (pinfunction "2_2") (pintype "passive"))
      (node (ref "J9") (pin "3") (pinfunction "3_3") (pintype "passive"))
      (node (ref "J9") (pin "4") (pinfunction "4_4") (pintype "passive"))
    )
    (net (code "19") (name "Net-(J10-Pad1)") (class "Default")
      (node (ref "J10") (pin "1") (pinfunction "1_1") (pintype "passive"))
      (node (ref "J10") (pin "2") (pinfunction "2_2") (pintype "passive"))
      (node (ref "J10") (pin "3") (pinfunction "3_3") (pintype "passive"))
      (node (ref "J10") (pin "4") (pinfunction "4_4") (pintype "passive"))
    )
    (net (code "20") (name "Net-(J11-Pad1)") (class "Default")
      (node (ref "J11") (pin "1") (pinfunction "1_1") (pintype "passive"))
      (node (ref "J11") (pin "2") (pinfunction "2_2") (pintype "passive"))
      (node (ref "J11") (pin "3") (pinfunction "3_3") (pintype "passive"))
      (node (ref "J11") (pin "4") (pinfunction "4_4") (pintype "passive"))
    )
    (net (code "21") (name "Net-(J12-Pad1)") (class "Default")
      (node (ref "J12") (pin "1") (pinfunction "1_1") (pintype "passive"))
      (node (ref "J12") (pin "2") (pinfunction "2_2") (pintype "passive"))
      (node (ref "J12") (pin "3") (pinfunction "3_3") (pintype "passive"))
      (node (ref "J12") (pin "4") (pinfunction "4_4") (pintype "passive"))
    )
    (net (code "22") (name "Net-(J13-Pad1)") (class "Default")
      (node (ref "J13") (pin "1") (pinfunction "1_1") (pintype "passive"))
      (node (ref "J13") (pin "2") (pinfunction "2_2") (pintype "passive"))
      (node (ref "J13") (pin "3") (pinfunction "3_3") (pintype "passive"))
      (node (ref "J13") (pin "4") (pinfunction "4_4") (pintype "passive"))
    )
    (net (code "23") (name "Net-(J14-Pad1)") (class "Default")
      (node (ref "J14") (pin "1") (pinfunction "1_1") (pintype "passive"))
      (node (ref "J14") (pin "2") (pinfunction "2_2") (pintype "passive"))
      (node (ref "J14") (pin "3") (pinfunction "3_3") (pintype "passive"))
      (node (ref "J14") (pin "4") (pinfunction "4_4") (pintype "passive"))
    )
    (net (code "24") (name "Net-(J15-Pad1)") (class "Default")
      (node (ref "J15") (pin "1") (pinfunction "1_1") (pintype "passive"))
      (node (ref "J15") (pin "2") (pinfunction "2_2") (pintype "passive"))
      (node (ref "J15") (pin "3") (pinfunction "3_3") (pintype "passive"))
      (node (ref "J15") (pin "4") (pinfunction "4_4") (pintype "passive"))
    )
    (net (code "25") (name "Net-(J16-Pad1)") (class "Default")
      (node (ref "J16") (pin "1") (pinfunction "1_1") (pintype "passive"))
      (node (ref "J16") (pin "2") (pinfunction "2_2") (pintype "passive"))
      (node (ref "J16") (pin "3") (pinfunction "3_3") (pintype "passive"))
      (node (ref "J16") (pin "4") (pinfunction "4_4") (pintype "passive"))
    )
    (net (code "26") (name "Net-(J17-Pad1)") (class "Default")
      (node (ref "J17") (pin "1") (pinfunction "1_1") (pintype "passive"))
      (node (ref "J17") (pin "2") (pinfunction "2_2") (pintype "passive"))
      (node (ref "J17") (pin "3") (pinfunction "3_3") (pintype "passive"))
      (node (ref "J17") (pin "4") (pinfunction "4_4") (pintype "passive"))
    )
    (net (code "27") (name "Net-(J18-Pad1)") (class "Default")
      (node (ref "J18") (pin "1") (pinfunction "1_1") (pintype "passive"))
      (node (ref "J18") (pin "2") (pinfunction "2_2") (pintype "passive"))
      (node (ref "J18") (pin "3") (pinfunction "3_3") (pintype "passive"))
      (node (ref "J18") (pin "4") (pinfunction "4_4") (pintype "passive"))
    )
    (net (code "28") (name "Net-(J19-Pad1)") (class "Default")
      (node (ref "J19") (pin "1") (pinfunction "1_1") (pintype "passive"))
      (node (ref "J19") (pin "2") (pinfunction "2_2") (pintype "passive"))
      (node (ref "J19") (pin "3") (pinfunction "3_3") (pintype "passive"))
      (node (ref "J19") (pin "4") (pinfunction "4_4") (pintype "passive"))
    )
    (net (code "29") (name "Net-(J20-Pad1)") (class "Default")
      (node (ref "J20") (pin "1") (pinfunction "1_1") (pintype "passive"))
      (node (ref "J20") (pin "2") (pinfunction "2_2") (pintype "passive"))
      (node (ref "J20") (pin "3") (pinfunction "3_3") (pintype "passive"))
      (node (ref "J20") (pin "4") (pinfunction "4_4") (pintype "passive"))
    )
    (net (code "30") (name "Net-(J21-Pad1)") (class "Default")
      (node (ref "J21") (pin "1") (pinfunction "1_1") (pintype "passive"))
      (node (ref "J21") (pin "2") (pinfunction "2_2") (pintype "passive"))
      (node (ref "J21") (pin "3") (pinfunction "3_3") (pintype "passive"))
      (node (ref "J21") (pin "4") (pinfunction "4_4") (pintype "passive"))
    )
    (net (code "31") (name "Net-(J22-Pad1)") (class "Default")
      (node (ref "J22") (pin "1") (pinfunction "1_1") (pintype "passive"))
      (node (ref "J22") (pin "2") (pinfunction "2_2") (pintype "passive"))
      (node (ref "J22") (pin "3") (pinfunction "3_3") (pintype "passive"))
      (node (ref "J22") (pin "4") (pinfunction "4_4") (pintype "passive"))
    )
    (net (code "32") (name "Net-(J23-Pad1)") (class "Default")
      (node (ref "J23") (pin "1") (pinfunction "1_1") (pintype "passive"))
      (node (ref "J23") (pin "2") (pinfunction "2_2") (pintype "passive"))
      (node (ref "J23") (pin "3") (pinfunction "3_3") (pintype "passive"))
      (node (ref "J23") (pin "4") (pinfunction "4_4") (pintype "passive"))
    )
    (net (code "33") (name "Net-(J24-Pad1)") (class "Default")
      (node (ref "J24") (pin "1") (pinfunction "1_1") (pintype "passive"))
      (node (ref "J24") (pin "2") (pinfunction "2_2") (pintype "passive"))
      (node (ref "J24") (pin "3") (pinfunction "3_3") (pintype "passive"))
      (node (ref "J24") (pin "4") (pinfunction "4_4") (pintype "passive"))
    )
    (net (code "34") (name "Net-(J25-Pad1)") (class "Default")
      (node (ref "J25") (pin "1") (pinfunction "1_1") (pintype "passive"))
      (node (ref "J25") (pin "2") (pinfunction "2_2") (pintype "passive"))
      (node (ref "J25") (pin "3") (pinfunction "3_3") (pintype "passive"))
      (node (ref "J25") (pin "4") (pinfunction "4_4") (pintype "passive"))
    )
    (net (code "35") (name "Net-(J26-Pad1)") (class "Default")
      (node (ref "J26") (pin "1") (pinfunction "1_1") (pintype "passive"))
      (node (ref "J26") (pin "2") (pinfunction "2_2") (pintype "passive"))
      (node (ref "J26") (pin "3") (pinfunction "3_3") (pintype "passive"))
      (node (ref "J26") (pin "4") (pinfunction "4_4") (pintype "passive"))
    )
    (net (code "36") (name "Net-(J27-Pad1)") (class "Default")
      (node (ref "J27") (pin "1") (pinfunction "1_1") (pintype "passive"))
      (node (ref "J27") (pin "2") (pinfunction "2_2") (pintype "passive"))
      (node (ref "J27") (pin "3") (pinfunction "3_3") (pintype "passive"))
      (node (ref "J27") (pin "4") (pinfunction "4_4") (pintype "passive"))
    )
    (net (code "37") (name "Net-(J28-Pad1)") (class "Default")
      (node (ref "J28") (pin "1") (pinfunction "1_1") (pintype "passive"))
      (node (ref "J28") (pin "2") (pinfunction "2_2") (pintype "passive"))
      (node (ref "J28") (pin "3") (pinfunction "3_3") (pintype "passive"))
      (node (ref "J28") (pin "4") (pinfunction "4_4") (pintype "passive"))
    )
    (net (code "38") (name "Net-(J29-Pad1)") (class "Default")
      (node (ref "J29") (pin "1") (pinfunction "1_1") (pintype "passive"))
      (node (ref "J29") (pin "2") (pinfunction "2_2") (pintype "passive"))
      (node (ref "J29") (pin "3") (pinfunction "3_3") (pintype "passive"))
      (node (ref "J29") (pin "4") (pinfunction "4_4") (pintype "passive"))
    )
    (net (code "39") (name "Net-(J30-Pad1)") (class "Default")
      (node (ref "J30") (pin "1") (pinfunction "1_1") (pintype "passive"))
      (node (ref "J30") (pin "2") (pinfunction "2_2") (pintype "passive"))
      (node (ref "J30") (pin "3") (pinfunction "3_3") (pintype "passive"))
      (node (ref "J30") (pin "4") (pinfunction "4_4") (pintype "passive"))
    )
    (net (code "40") (name "Net-(J31-Pad1)") (class "Default")
      (node (ref "J31") (pin "1") (pinfunction "1_1") (pintype "passive"))
      (node (ref "J31") (pin "2") (pinfunction "2_2") (pintype "passive"))
      (node (ref "J31") (pin "3") (pinfunction "3_3") (pintype "passive"))
      (node (ref "J31") (pin "4") (pinfunction "4_4") (pintype "passive"))
    )
    (net (code "41") (name "Net-(J32-Pad1)") (class "Default")
      (node (ref "J32") (pin "1") (pinfunction "1_1") (pintype "passive"))
      (node (ref "J32") (pin "2") (pinfunction "2_2") (pintype "passive"))
      (node (ref "J32") (pin "3") (pinfunction "3_3") (pintype "passive"))
      (node (ref "J32") (pin "4") (pinfunction "4_4") (pintype "passive"))
    )
    (net (code "42") (name "Net-(J33-Pad1)") (class "Default")
      (node (ref "J33") (pin "1") (pinfunction "1_1") (pintype "passive"))
      (node (ref "J33") (pin "2") (pinfunction "2_2") (pintype "passive"))
      (node (ref "J33") (pin "3") (pinfunction "3_3") (pintype "passive"))
      (node (ref "J33") (pin "4") (pinfunction "4_4") (pintype "passive"))
    )
    (net (code "43") (name "Net-(J34-Pad1)") (class "Default")
      (node (ref "J34") (pin "1") (pinfunction "1_1") (pintype "passive"))
      (node (ref "J34") (pin "2") (pinfunction "2_2") (pintype "passive"))
      (node (ref "J34") (pin "3") (pinfunction "3_3") (pintype "passive"))
      (node (ref "J34") (pin "4") (pinfunction "4_4") (pintype "passive"))
    )
    (net (code "44") (name "Net-(J35-Pad1)") (class "Default")
      (node (ref "J35") (pin "1") (pinfunction "1_1") (pintype "passive"))
      (node (ref "J35") (pin "2") (pinfunction "2_2") (pintype "passive"))
      (node (ref "J35") (pin "3") (pinfunction "3_3") (pintype "passive"))
      (node (ref "J35") (pin "4") (pinfunction "4_4") (pintype "passive"))
    )
    (net (code "45") (name "Net-(J36-Pad1)") (class "Default")
      (node (ref "J36") (pin "1") (pinfunction "1_1") (pintype "passive"))
      (node (ref "J36") (pin "2") (pinfunction "2_2") (pintype "passive"))
      (node (ref "J36") (pin "3") (pinfunction "3_3") (pintype "passive"))
      (node (ref "J36") (pin "4") (pinfunction "4_4") (pintype "passive"))
    )
    (net (code "46") (name "Net-(J37-Pad1)") (class "Default")
      (node (ref "J37") (pin "1") (pinfunction "1_1") (pintype "passive"))
      (node (ref "J37") (pin "2") (pinfunction "2_2") (pintype "passive"))
      (node (ref "J37") (pin "3") (pinfunction "3_3") (pintype "passive"))
      (node (ref "J37") (pin "4") (pinfunction "4_4") (pintype "passive"))
    )
    (net (code "47") (name "Net-(J38-Pad1)") (class "Default")
      (node (ref "J38") (pin "1") (pinfunction "1_1") (pintype "passive"))
      (node (ref "J38") (pin "2") (pinfunction "2_2") (pintype "passive"))
      (node (ref "J38") (pin "3") (pinfunction "3_3") (pintype "passive"))
      (node (ref "J38") (pin "4") (pinfunction "4_4") (pintype "passive"))
    )
    (net (code "48") (name "Net-(J39-Pad1)") (class "Default")
      (node (ref "J39") (pin "1") (pinfunction "1_1") (pintype "passive"))
      (node (ref "J39") (pin "2") (pinfunction "2_2") (pintype "passive"))
      (node (ref "J39") (pin "3") (pinfunction "3_3") (pintype "passive"))
      (node (ref "J39") (pin "4") (pinfunction "4_4") (pintype "passive"))
    )
    (net (code "49") (name "Net-(J40-Pad1)") (class "Default")
      (node (ref "J40") (pin "1") (pinfunction "1_1") (pintype "passive"))
      (node (ref "J40") (pin "2") (pinfunction "2_2") (pintype "passive"))
      (node (ref "J40") (pin "3") (pinfunction "3_3") (pintype "passive"))
      (node (ref "J40") (pin "4") (pinfunction "4_4") (pintype "passive"))
    )
    (net (code "50") (name "Net-(J41-Pad1)") (class "Default")
      (node (ref "J41") (pin "1") (pinfunction "1_1") (pintype "passive"))
      (node (ref "J41") (pin "2") (pinfunction "2_2") (pintype "passive"))
      (node (ref "J41") (pin "3") (pinfunction "3_3") (pintype "passive"))
      (node (ref "J41") (pin "4") (pinfunction "4_4") (pintype "passive"))
    )
    (net (code "51") (name "Net-(J42-Pad1)") (class "Default")
      (node (ref "J42") (pin "1") (pinfunction "1_1") (pintype "passive"))
      (node (ref "J42") (pin "2") (pinfunction "2_2") (pintype "passive"))
      (node (ref "J42") (pin "3") (pinfunction "3_3") (pintype "passive"))
      (node (ref "J42") (pin "4") (pinfunction "4_4") (pintype "passive"))
    )
    (net (code "52") (name "Net-(J43-Pad1)") (class "Default")
      (node (ref "J43") (pin "1") (pinfunction "1_1") (pintype "passive"))
      (node (ref "J43") (pin "2") (pinfunction "2_2") (pintype "passive"))
      (node (ref "J43") (pin "3") (pinfunction "3_3") (pintype "passive"))
      (node (ref "J43") (pin "4") (pinfunction "4_4") (pintype "passive"))
    )
    (net (code "53") (name "Net-(J44-Pad1)") (class "Default")
      (node (ref "J44") (pin "1") (pinfunction "1_1") (pintype "passive"))
      (node (ref "J44") (pin "2") (pinfunction "2_2") (pintype "passive"))
      (node (ref "J44") (pin "3") (pinfunction "3_3") (pintype "passive"))
      (node (ref "J44") (pin "4") (pinfunction "4_4") (pintype "passive"))
    )
    (net (code "54") (name "Net-(J45-Pad1)") (class "Default")
      (node (ref "J45") (pin "1") (pinfunction "1_1") (pintype "passive"))
      (node (ref "J45") (pin "2") (pinfunction "2_2") (pintype "passive"))
      (node (ref "J45") (pin "3") (pinfunction "3_3") (pintype "passive"))
      (node (ref "J45") (pin "4") (pinfunction "4_4") (pintype "passive"))
    )
    (net (code "55") (name "Net-(J46-Pad1)") (class "Default")
      (node (ref "J46") (pin "1") (pinfunction "1_1") (pintype "passive"))
      (node (ref "J46") (pin "2") (pinfunction "2_2") (pintype "passive"))
      (node (ref "J46") (pin "3") (pinfunction "3_3") (pintype "passive"))
      (node (ref "J46") (pin "4") (pinfunction "4_4") (pintype "passive"))
    )
    (net (code "56") (name "Net-(J47-Pad1)") (class "Default")
      (node (ref "J47") (pin "1") (pinfunction "1_1") (pintype "passive"))
      (node (ref "J47") (pin "2") (pinfunction "2_2") (pintype "passive"))
      (node (ref "J47") (pin "3") (pinfunction "3_3") (pintype "passive"))
      (node (ref "J47") (pin "4") (pinfunction "4_4") (pintype "passive"))
    )
    (net (code "57") (name "Net-(J48-Pad1)") (class "Default")
      (node (ref "J48") (pin "1") (pinfunction "1_1") (pintype "passive"))
      (node (ref "J48") (pin "2") (pinfunction "2_2") (pintype "passive"))
      (node (ref "J48") (pin "3") (pinfunction "3_3") (pintype "passive"))
      (node (ref "J48") (pin "4") (pinfunction "4_4") (pintype "passive"))
    )
    (net (code "58") (name "Net-(J49-Pad1)") (class "Default")
      (node (ref "J49") (pin "1") (pinfunction "1_1") (pintype "passive"))
      (node (ref "J49") (pin "2") (pinfunction "2_2") (pintype "passive"))
      (node (ref "J49") (pin "3") (pinfunction "3_3") (pintype "passive"))
      (node (ref "J49") (pin "4") (pinfunction "4_4") (pintype "passive"))
    )
    (net (code "59") (name "Net-(J50-Pad1)") (class "Default")
      (node (ref "J50") (pin "1") (pinfunction "1_1") (pintype "passive"))
      (node (ref "J50") (pin "2") (pinfunction "2_2") (pintype "passive"))
      (node (ref "J50") (pin "3") (pinfunction "3_3") (pintype "passive"))
      (node (ref "J50") (pin "4") (pinfunction "4_4") (pintype "passive"))
    )
    (net (code "60") (name "Net-(J51-Pad1)") (class "Default")
      (node (ref "J51") (pin "1") (pinfunction "1_1") (pintype "passive"))
      (node (ref "J51") (pin "2") (pinfunction "2_2") (pintype "passive"))
      (node (ref "J51") (pin "3") (pinfunction "3_3") (pintype "passive"))
      (node (ref "J51") (pin "4") (pinfunction "4_4") (pintype "passive"))
    )
  )
)
